# schematic.net
KiCad netlist of a schematic drawn in Altium Designer
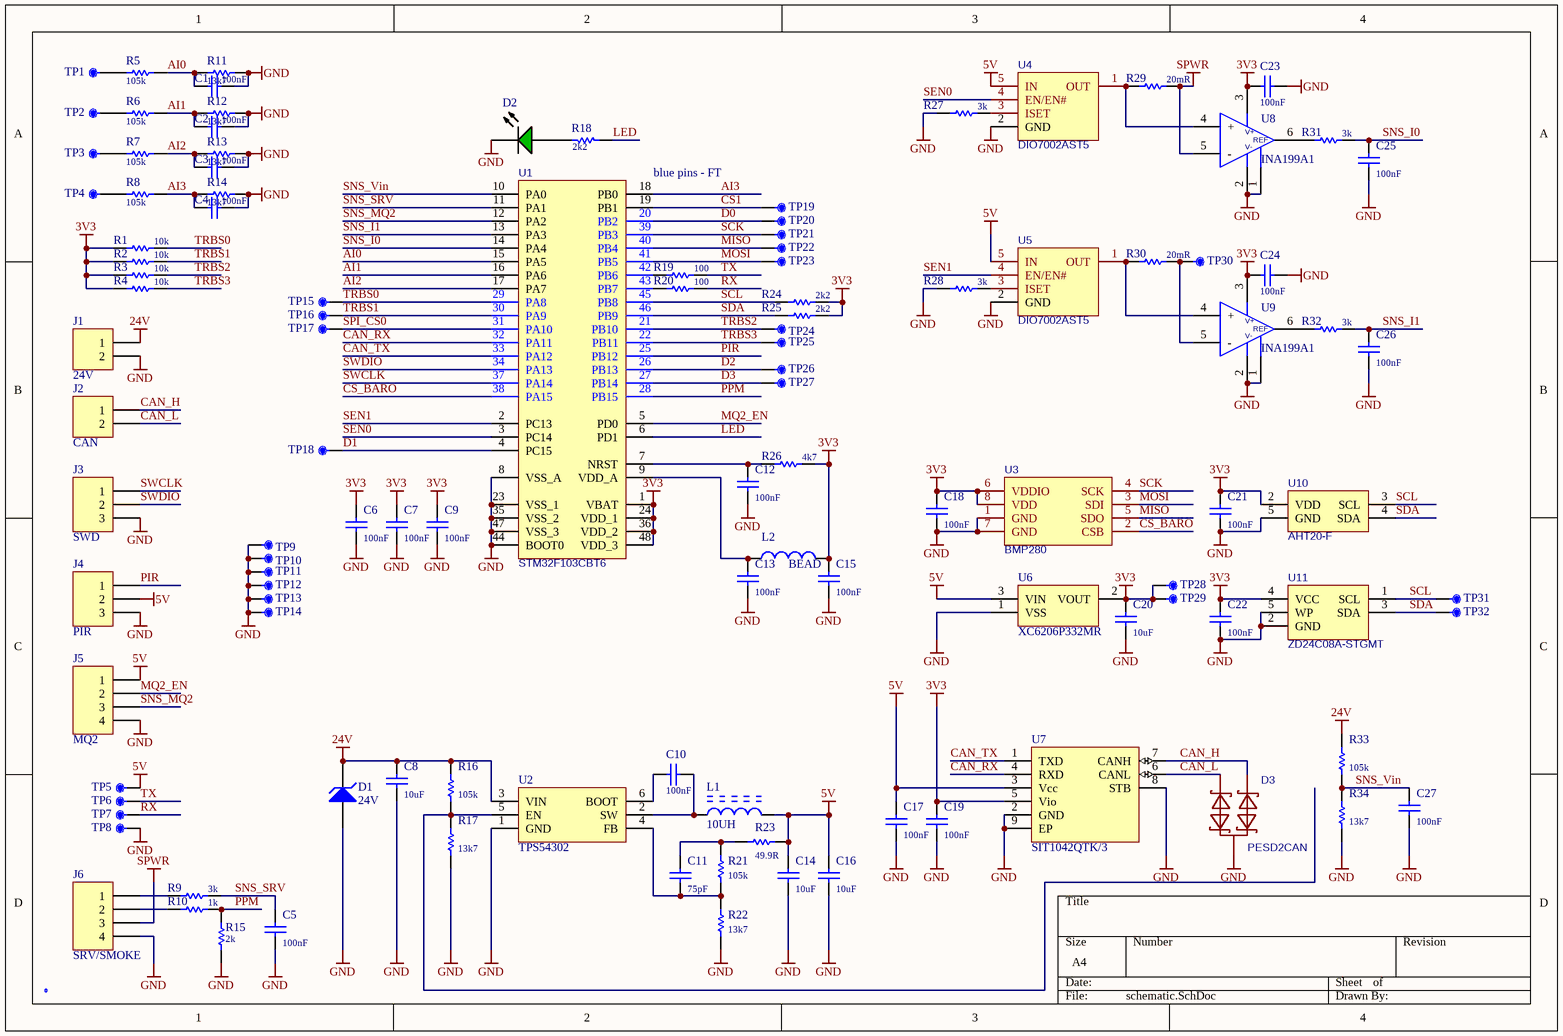
[diagram p0: schematic.SchDoc]

(export (version "E")
  (design (tool "Eeschema 10.0.6"))
  (components
    (comp (ref "C1")
      (value "100nF")
      (footprint "C0402")
      (description "100nF 50V 0402")
      (fields (field (name "LCSC PART NUMBER") "C110251"))
      (libsource (lib "Miscellaneous Devices") (part "CAP"))
    )
    (comp (ref "C2")
      (value "100nF")
      (footprint "C0402")
      (description "100nF 50V 0402")
      (fields (field (name "LCSC PART NUMBER") "C110251"))
      (libsource (lib "Miscellaneous Devices") (part "CAP"))
    )
    (comp (ref "C3")
      (value "100nF")
      (footprint "C0402")
      (description "100nF 50V 0402")
      (fields (field (name "LCSC PART NUMBER") "C110251"))
      (libsource (lib "Miscellaneous Devices") (part "CAP"))
    )
    (comp (ref "C4")
      (value "100nF")
      (footprint "C0402")
      (description "100nF 50V 0402")
      (fields (field (name "LCSC PART NUMBER") "C110251"))
      (libsource (lib "Miscellaneous Devices") (part "CAP"))
    )
    (comp (ref "C5")
      (value "100nF")
      (footprint "C0402")
      (description "100nF 50V 0402")
      (fields (field (name "LCSC PART NUMBER") "C110251"))
      (libsource (lib "Miscellaneous Devices") (part "CAP"))
    )
    (comp (ref "C6")
      (value "100nF")
      (footprint "C0402")
      (description "100nF 50V 0402")
      (fields (field (name "LCSC PART NUMBER") "C110251"))
      (libsource (lib "Miscellaneous Devices") (part "CAP"))
    )
    (comp (ref "C7")
      (value "100nF")
      (footprint "C0402")
      (description "100nF 50V 0402")
      (fields (field (name "LCSC PART NUMBER") "C110251"))
      (libsource (lib "Miscellaneous Devices") (part "CAP"))
    )
    (comp (ref "C8")
      (value "10uF")
      (footprint "C1206")
      (description "10uf 50V 1206")
      (fields (field (name "LCSC PART NUMBER") "C89632"))
      (libsource (lib "Miscellaneous Devices") (part "CAP"))
    )
    (comp (ref "C9")
      (value "100nF")
      (footprint "C0402")
      (description "100nF 50V 0402")
      (fields (field (name "LCSC PART NUMBER") "C110251"))
      (libsource (lib "Miscellaneous Devices") (part "CAP"))
    )
    (comp (ref "C10")
      (value "100nF")
      (footprint "C0402")
      (description "100nF 50V 0402")
      (fields (field (name "LCSC PART NUMBER") "C110251"))
      (libsource (lib "Miscellaneous Devices") (part "CAP"))
    )
    (comp (ref "C11")
      (value "75pF")
      (footprint "C0402")
      (description "75pF 50V 0402")
      (fields (field (name "LCSC PART NUMBER") "C107010"))
      (libsource (lib "Miscellaneous Devices") (part "CAP"))
    )
    (comp (ref "C12")
      (value "100nF")
      (footprint "C0402")
      (description "100nF 50V 0402")
      (fields (field (name "LCSC PART NUMBER") "C110251"))
      (libsource (lib "Miscellaneous Devices") (part "CAP"))
    )
    (comp (ref "C13")
      (value "100nF")
      (footprint "C0402")
      (description "100nF 50V 0402")
      (fields (field (name "LCSC PART NUMBER") "C110251"))
      (libsource (lib "Miscellaneous Devices") (part "CAP"))
    )
    (comp (ref "C14")
      (value "10uF")
      (footprint "C1206")
      (description "10uf 50V 1206")
      (fields (field (name "LCSC PART NUMBER") "C89632"))
      (libsource (lib "Miscellaneous Devices") (part "CAP"))
    )
    (comp (ref "C15")
      (value "100nF")
      (footprint "C0402")
      (description "100nF 50V 0402")
      (fields (field (name "LCSC PART NUMBER") "C110251"))
      (libsource (lib "Miscellaneous Devices") (part "CAP"))
    )
    (comp (ref "C16")
      (value "10uF")
      (footprint "C1206")
      (description "10uf 50V 1206")
      (fields (field (name "LCSC PART NUMBER") "C89632"))
      (libsource (lib "Miscellaneous Devices") (part "CAP"))
    )
    (comp (ref "C17")
      (value "100nF")
      (footprint "C0402")
      (description "100nF 50V 0402")
      (fields (field (name "LCSC PART NUMBER") "C110251"))
      (libsource (lib "Miscellaneous Devices") (part "CAP"))
    )
    (comp (ref "C18")
      (value "100nF")
      (footprint "C0402")
      (description "100nF 50V 0402")
      (fields (field (name "LCSC PART NUMBER") "C110251"))
      (libsource (lib "Miscellaneous Devices") (part "CAP"))
    )
    (comp (ref "C19")
      (value "100nF")
      (footprint "C0402")
      (description "100nF 50V 0402")
      (fields (field (name "LCSC PART NUMBER") "C110251"))
      (libsource (lib "Miscellaneous Devices") (part "CAP"))
    )
    (comp (ref "C20")
      (value "10uF")
      (footprint "C1206")
      (description "10uf 50V 1206")
      (fields (field (name "LCSC PART NUMBER") "C89632"))
      (libsource (lib "Miscellaneous Devices") (part "CAP"))
    )
    (comp (ref "C21")
      (value "100nF")
      (footprint "C0402")
      (description "100nF 50V 0402")
      (fields (field (name "LCSC PART NUMBER") "C110251"))
      (libsource (lib "Miscellaneous Devices") (part "CAP"))
    )
    (comp (ref "C22")
      (value "100nF")
      (footprint "C0402")
      (description "100nF 50V 0402")
      (fields (field (name "LCSC PART NUMBER") "C110251"))
      (libsource (lib "Miscellaneous Devices") (part "CAP"))
    )
    (comp (ref "C23")
      (value "100nF")
      (footprint "C0402")
      (description "100nF 50V 0402")
      (fields (field (name "LCSC PART NUMBER") "C110251"))
      (libsource (lib "Miscellaneous Devices") (part "CAP"))
    )
    (comp (ref "C24")
      (value "100nF")
      (footprint "C0402")
      (description "100nF 50V 0402")
      (fields (field (name "LCSC PART NUMBER") "C110251"))
      (libsource (lib "Miscellaneous Devices") (part "CAP"))
    )
    (comp (ref "C25")
      (value "100nF")
      (footprint "C0402")
      (description "100nF 50V 0402")
      (fields (field (name "LCSC PART NUMBER") "C110251"))
      (libsource (lib "Miscellaneous Devices") (part "CAP"))
    )
    (comp (ref "C26")
      (value "100nF")
      (footprint "C0402")
      (description "100nF 50V 0402")
      (fields (field (name "LCSC PART NUMBER") "C110251"))
      (libsource (lib "Miscellaneous Devices") (part "CAP"))
    )
    (comp (ref "C27")
      (value "100nF")
      (footprint "C0402")
      (description "100nF 50V 0402")
      (fields (field (name "LCSC PART NUMBER") "C110251"))
      (libsource (lib "Miscellaneous Devices") (part "CAP"))
    )
    (comp (ref "D1")
      (value "24V")
      (footprint "SMB")
      (description "P6SMB24A")
      (fields (field (name "LCSC PART NUMBER") "C5155417"))
      (libsource (lib "Miscellaneous Devices") (part "SMCJ54A"))
    )
    (comp (ref "D2")
      (value "GRN")
      (footprint "LED-0603-GRN")
      (description "LED 0603 GRN")
      (fields (field (name "LCSC PART NUMBER") "C434423"))
      (libsource (lib "Miscellaneous Devices") (part "LED-0603-GREEN"))
    )
    (comp (ref "D3")
      (value "PESD2CAN")
      (footprint "SOT-23")
      (fields (field (name "LCSC PART NUMBER") "C5261081"))
      (libsource (lib "Miscellaneous Devices") (part "CDSOT23-SM712"))
    )
    (comp (ref "J1")
      (value "24V")
      (footprint "CONN_DG308-2.54-2P")
      (description "DG308-2.54-02P-14-00A(H)")
      (fields (field (name "LCSC PART NUMBER") "C699496"))
      (libsource (lib "Miscellaneous Devices") (part "CONN MOLEX HDR-M 1x4"))
    )
    (comp (ref "J2")
      (value "CAN")
      (footprint "CONN_DG308-2.54-2P")
      (description "DG308-2.54-02P-14-00A(H)")
      (fields (field (name "LCSC PART NUMBER") "C699496"))
      (libsource (lib "Miscellaneous Devices") (part "CONN MOLEX HDR-M 1x4"))
    )
    (comp (ref "J3")
      (value "SWD")
      (footprint "SWD")
      (libsource (lib "Miscellaneous Devices") (part "Header 3"))
    )
    (comp (ref "J4")
      (value "PIR")
      (footprint "CONN_MOLEX_532610371")
      (libsource (lib "Miscellaneous Devices") (part "Header 3"))
    )
    (comp (ref "J5")
      (value "MQ2")
      (footprint "CONN_MOLEX_532610471")
      (libsource (lib "Schlib1") (part "Header 3"))
    )
    (comp (ref "J6") (value "SRV/SMOKE") (footprint "HDR-1X4") (libsource (lib "Schlib1") (part "Header 3")))
    (comp (ref "L1")
      (value "10UH")
      (footprint "IND-SMD_L7.2-W6.6_GPSR07X0")
      (description "CYA0630-10UH")
      (fields (field (name "LCSC PART NUMBER") "C5189958"))
      (libsource (lib "Miscellaneous Devices") (part "SRN3015-100M"))
    )
    (comp (ref "L2")
      (value "BEAD")
      (footprint "L0402")
      (description "BEAD 0402")
      (fields (field (name "LCSC PART NUMBER") "C76883"))
      (libsource (lib "Miscellaneous Devices") (part "BLM18AG601SN1D"))
    )
    (comp (ref "LOGO1") (value "LOGO") (footprint "LOGO") (libsource (lib "Schlib1") (part "LOGO")))
    (comp (ref "R1")
      (value "10k")
      (footprint "R0402")
      (description "10k 0402")
      (fields (field (name "LCSC PART NUMBER") "C25744"))
      (libsource (lib "Miscellaneous Devices") (part "RES"))
    )
    (comp (ref "R2")
      (value "10k")
      (footprint "R0402")
      (description "10k 0402")
      (fields (field (name "LCSC PART NUMBER") "C25744"))
      (libsource (lib "Miscellaneous Devices") (part "RES"))
    )
    (comp (ref "R3")
      (value "10k")
      (footprint "R0402")
      (description "10k 0402")
      (fields (field (name "LCSC PART NUMBER") "C25744"))
      (libsource (lib "Miscellaneous Devices") (part "RES"))
    )
    (comp (ref "R4")
      (value "10k")
      (footprint "R0402")
      (description "10k 0402")
      (fields (field (name "LCSC PART NUMBER") "C25744"))
      (libsource (lib "Miscellaneous Devices") (part "RES"))
    )
    (comp (ref "R5")
      (value "105k")
      (footprint "R0402")
      (description "105k 0402")
      (fields (field (name "LCSC PART NUMBER") "C170210"))
      (libsource (lib "Miscellaneous Devices") (part "RES"))
    )
    (comp (ref "R6")
      (value "105k")
      (footprint "R0402")
      (description "105k 0402")
      (fields (field (name "LCSC PART NUMBER") "C170210"))
      (libsource (lib "Miscellaneous Devices") (part "RES"))
    )
    (comp (ref "R7")
      (value "105k")
      (footprint "R0402")
      (description "105k 0402")
      (fields (field (name "LCSC PART NUMBER") "C170210"))
      (libsource (lib "Miscellaneous Devices") (part "RES"))
    )
    (comp (ref "R8")
      (value "105k")
      (footprint "R0402")
      (description "105k 0402")
      (fields (field (name "LCSC PART NUMBER") "C170210"))
      (libsource (lib "Miscellaneous Devices") (part "RES"))
    )
    (comp (ref "R9")
      (value "3k")
      (footprint "R0402")
      (description "3k 0402")
      (fields (field (name "LCSC PART NUMBER") "C25784"))
      (libsource (lib "") (part "RES_1"))
    )
    (comp (ref "R10")
      (value "1k")
      (footprint "R0402")
      (description "1k 0402")
      (fields (field (name "LCSC PART NUMBER") "C11702"))
      (libsource (lib "Miscellaneous Devices") (part "RES"))
    )
    (comp (ref "R11")
      (value "13k7")
      (footprint "R0402")
      (description "13k7 0402")
      (fields (field (name "LCSC PART NUMBER") "C2933072"))
      (libsource (lib "Miscellaneous Devices") (part "RES"))
    )
    (comp (ref "R12")
      (value "13k7")
      (footprint "R0402")
      (description "13k7 0402")
      (fields (field (name "LCSC PART NUMBER") "C2933072"))
      (libsource (lib "Miscellaneous Devices") (part "RES"))
    )
    (comp (ref "R13")
      (value "13k7")
      (footprint "R0402")
      (description "13k7 0402")
      (fields (field (name "LCSC PART NUMBER") "C2933072"))
      (libsource (lib "Miscellaneous Devices") (part "RES"))
    )
    (comp (ref "R14")
      (value "13k7")
      (footprint "R0402")
      (description "13k7 0402")
      (fields (field (name "LCSC PART NUMBER") "C2933072"))
      (libsource (lib "Miscellaneous Devices") (part "RES"))
    )
    (comp (ref "R15")
      (value "2k")
      (footprint "R0402")
      (description "2k 0402")
      (fields (field (name "LCSC PART NUMBER") "C4109"))
      (libsource (lib "Miscellaneous Devices") (part "RES"))
    )
    (comp (ref "R16")
      (value "105k")
      (footprint "R0402")
      (description "105k 0402")
      (fields (field (name "LCSC PART NUMBER") "C170210"))
      (libsource (lib "Miscellaneous Devices") (part "RES"))
    )
    (comp (ref "R17")
      (value "13k7")
      (footprint "R0402")
      (description "13k7 0402")
      (fields (field (name "LCSC PART NUMBER") "C2933072"))
      (libsource (lib "Miscellaneous Devices") (part "RES"))
    )
    (comp (ref "R18")
      (value "2k2")
      (footprint "R0402")
      (description "2k 0402")
      (fields (field (name "LCSC PART NUMBER") "C4109"))
      (libsource (lib "Miscellaneous Devices") (part "RES"))
    )
    (comp (ref "R19")
      (value "100")
      (footprint "R0402")
      (description "100 0402")
      (fields (field (name "LCSC PART NUMBER") "C25076"))
      (libsource (lib "Miscellaneous Devices") (part "RES"))
    )
    (comp (ref "R20")
      (value "100")
      (footprint "R0402")
      (description "100 0402")
      (fields (field (name "LCSC PART NUMBER") "C25076"))
      (libsource (lib "Miscellaneous Devices") (part "RES"))
    )
    (comp (ref "R21")
      (value "105k")
      (footprint "R0402")
      (description "105k 0402")
      (fields (field (name "LCSC PART NUMBER") "C170210"))
      (libsource (lib "Miscellaneous Devices") (part "RES"))
    )
    (comp (ref "R22")
      (value "13k7")
      (footprint "R0402")
      (description "13k7 0402")
      (fields (field (name "LCSC PART NUMBER") "C2933072"))
      (libsource (lib "Miscellaneous Devices") (part "RES"))
    )
    (comp (ref "R23")
      (value "49.9R")
      (footprint "R0402")
      (description "49R9 0402")
      (fields (field (name "LCSC PART NUMBER") "C87044"))
      (libsource (lib "") (part "RES_2"))
    )
    (comp (ref "R24")
      (value "2k2")
      (footprint "R0402")
      (description "2k 0402")
      (fields (field (name "LCSC PART NUMBER") "C4109"))
      (libsource (lib "Miscellaneous Devices") (part "RES"))
    )
    (comp (ref "R25")
      (value "2k2")
      (footprint "R0402")
      (description "2k 0402")
      (fields (field (name "LCSC PART NUMBER") "C4109"))
      (libsource (lib "Miscellaneous Devices") (part "RES"))
    )
    (comp (ref "R26")
      (value "4k7")
      (footprint "R0402")
      (description "4k7 0402")
      (fields (field (name "LCSC PART NUMBER") "C25900"))
      (libsource (lib "Miscellaneous Devices") (part "RES"))
    )
    (comp (ref "R27")
      (value "3k")
      (footprint "R0402")
      (description "3k 0402")
      (fields (field (name "LCSC PART NUMBER") "C25784"))
      (libsource (lib "") (part "RES_1"))
    )
    (comp (ref "R28")
      (value "3k")
      (footprint "R0402")
      (description "3k 0402")
      (fields (field (name "LCSC PART NUMBER") "C25784"))
      (libsource (lib "") (part "RES_1"))
    )
    (comp (ref "R29")
      (value "20mR")
      (footprint "R0805")
      (description "0805W4F200MT5E")
      (fields (field (name "LCSC PART NUMBER") "C7467520"))
      (libsource (lib "") (part "RES_1"))
    )
    (comp (ref "R30")
      (value "20mR")
      (footprint "R0805")
      (description "0805W4F200MT5E")
      (fields (field (name "LCSC PART NUMBER") "C7467520"))
      (libsource (lib "") (part "RES_1"))
    )
    (comp (ref "R31")
      (value "3k")
      (footprint "R0402")
      (description "3k 0402")
      (fields (field (name "LCSC PART NUMBER") "C25784"))
      (libsource (lib "Miscellaneous Devices") (part "RES"))
    )
    (comp (ref "R32")
      (value "3k")
      (footprint "R0402")
      (description "3k 0402")
      (fields (field (name "LCSC PART NUMBER") "C25784"))
      (libsource (lib "Miscellaneous Devices") (part "RES"))
    )
    (comp (ref "R33")
      (value "105k")
      (footprint "R0402")
      (description "105k 0402")
      (fields (field (name "LCSC PART NUMBER") "C170210"))
      (libsource (lib "Miscellaneous Devices") (part "RES"))
    )
    (comp (ref "R34")
      (value "13k7")
      (footprint "R0402")
      (description "13k7 0402")
      (fields (field (name "LCSC PART NUMBER") "C2933072"))
      (libsource (lib "Miscellaneous Devices") (part "RES"))
    )
    (comp (ref "TP1")
      (value "~")
      (footprint "TP_TH_S0")
      (libsource (lib "Miscellaneous Devices") (part "TP_Dup1"))
    )
    (comp (ref "TP2")
      (value "~")
      (footprint "TP_TH_S0")
      (libsource (lib "Miscellaneous Devices") (part "TP_Dup1"))
    )
    (comp (ref "TP3")
      (value "~")
      (footprint "TP_TH_S0")
      (libsource (lib "Miscellaneous Devices") (part "TP_Dup1"))
    )
    (comp (ref "TP4")
      (value "~")
      (footprint "TP_TH_S0")
      (libsource (lib "Miscellaneous Devices") (part "TP_Dup1"))
    )
    (comp (ref "TP5")
      (value "~")
      (footprint "TP_TH_S0")
      (libsource (lib "Miscellaneous Devices") (part "TP_Dup1"))
    )
    (comp (ref "TP6")
      (value "~")
      (footprint "TP_TH_S0")
      (libsource (lib "Miscellaneous Devices") (part "TP_Dup1"))
    )
    (comp (ref "TP7")
      (value "~")
      (footprint "TP_TH_S0")
      (libsource (lib "Miscellaneous Devices") (part "TP_Dup1"))
    )
    (comp (ref "TP8")
      (value "~")
      (footprint "TP_TH_S0")
      (libsource (lib "Miscellaneous Devices") (part "TP_Dup1"))
    )
    (comp (ref "TP9")
      (value "~")
      (footprint "TP_TH_S0")
      (libsource (lib "Miscellaneous Devices") (part "TP_Dup1"))
    )
    (comp (ref "TP10")
      (value "~")
      (footprint "TP_TH_S0")
      (libsource (lib "Miscellaneous Devices") (part "TP_Dup1"))
    )
    (comp (ref "TP11")
      (value "~")
      (footprint "TP_TH_S0")
      (libsource (lib "Miscellaneous Devices") (part "TP_Dup1"))
    )
    (comp (ref "TP12")
      (value "~")
      (footprint "TP_TH_S0")
      (libsource (lib "Miscellaneous Devices") (part "TP_Dup1"))
    )
    (comp (ref "TP13")
      (value "~")
      (footprint "TP_TH_S0")
      (libsource (lib "Miscellaneous Devices") (part "TP_Dup1"))
    )
    (comp (ref "TP14")
      (value "~")
      (footprint "TP_TH_S0")
      (libsource (lib "Miscellaneous Devices") (part "TP_Dup1"))
    )
    (comp (ref "TP15")
      (value "~")
      (footprint "TP_TH_S0")
      (libsource (lib "Miscellaneous Devices") (part "TP_Dup1"))
    )
    (comp (ref "TP16")
      (value "~")
      (footprint "TP_TH_S0")
      (libsource (lib "Miscellaneous Devices") (part "TP_Dup1"))
    )
    (comp (ref "TP17")
      (value "~")
      (footprint "TP_TH_S0")
      (libsource (lib "Miscellaneous Devices") (part "TP_Dup1"))
    )
    (comp (ref "TP18")
      (value "~")
      (footprint "TP_TH_S0")
      (libsource (lib "Miscellaneous Devices") (part "TP_Dup1"))
    )
    (comp (ref "TP19")
      (value "~")
      (footprint "TP_TH_S0")
      (libsource (lib "Miscellaneous Devices") (part "TP_Dup1"))
    )
    (comp (ref "TP20")
      (value "~")
      (footprint "TP_TH_S0")
      (libsource (lib "Miscellaneous Devices") (part "TP_Dup1"))
    )
    (comp (ref "TP21")
      (value "~")
      (footprint "TP_TH_S0")
      (libsource (lib "Miscellaneous Devices") (part "TP_Dup1"))
    )
    (comp (ref "TP22")
      (value "~")
      (footprint "TP_TH_S0")
      (libsource (lib "Miscellaneous Devices") (part "TP_Dup1"))
    )
    (comp (ref "TP23")
      (value "~")
      (footprint "TP_TH_S0")
      (libsource (lib "Miscellaneous Devices") (part "TP_Dup1"))
    )
    (comp (ref "TP24")
      (value "~")
      (footprint "TP_TH_S0")
      (libsource (lib "Miscellaneous Devices") (part "TP_Dup1"))
    )
    (comp (ref "TP25")
      (value "~")
      (footprint "TP_TH_S0")
      (libsource (lib "Miscellaneous Devices") (part "TP_Dup1"))
    )
    (comp (ref "TP26")
      (value "~")
      (footprint "TP_TH_S0")
      (libsource (lib "Miscellaneous Devices") (part "TP_Dup1"))
    )
    (comp (ref "TP27")
      (value "~")
      (footprint "TP_TH_S0")
      (libsource (lib "Miscellaneous Devices") (part "TP_Dup1"))
    )
    (comp (ref "TP28")
      (value "~")
      (footprint "TP_TH_S0")
      (libsource (lib "Miscellaneous Devices") (part "TP_Dup1"))
    )
    (comp (ref "TP29")
      (value "~")
      (footprint "TP_TH_S0")
      (libsource (lib "Miscellaneous Devices") (part "TP_Dup1"))
    )
    (comp (ref "TP30")
      (value "~")
      (footprint "TP_TH_S0")
      (libsource (lib "Miscellaneous Devices") (part "TP_Dup1"))
    )
    (comp (ref "TP31")
      (value "~")
      (footprint "TP_TH_S0")
      (libsource (lib "Miscellaneous Devices") (part "TP_Dup1"))
    )
    (comp (ref "TP32")
      (value "~")
      (footprint "TP_TH_S0")
      (libsource (lib "Miscellaneous Devices") (part "TP_Dup1"))
    )
    (comp (ref "U1")
      (value "STM32F103CBT6")
      (footprint "LQFP-48")
      (fields (field (name "LCSC PART NUMBER") "C8304"))
      (libsource (lib "Schlib1") (part "STM32F103CBT6"))
    )
    (comp (ref "U2")
      (value "TPS54302")
      (footprint "SOT-23-6")
      (description "TPS54302DDCR")
      (fields (field (name "LCSC PART NUMBER") "C311983"))
      (libsource (lib "Miscellaneous Devices") (part "LM27313XMFX"))
    )
    (comp (ref "U3")
      (value "BMP280")
      (footprint "WLGA-8_L2.5-W2.0-P0.65-TR_DPS422")
      (fields (field (name "LCSC PART NUMBER") "C83291"))
      (libsource (lib "Schlib1") (part "BMP280"))
    )
    (comp (ref "U4")
      (value "DIO7002AST5")
      (footprint "SOT-23-5")
      (fields (field (name "LCSC PART NUMBER") "C403840"))
      (libsource (lib "Schlib1") (part "DIO7002AST5"))
    )
    (comp (ref "U5")
      (value "DIO7002AST5")
      (footprint "SOT-23-5")
      (fields (field (name "LCSC PART NUMBER") "C403840"))
      (libsource (lib "Schlib1") (part "DIO7002AST5"))
    )
    (comp (ref "U6")
      (value "XC6206P332MR")
      (footprint "SOT-23")
      (fields (field (name "LCSC PART NUMBER") "C5148692"))
      (libsource (lib "Schlib1") (part "Component_4_1"))
    )
    (comp (ref "U7")
      (value "SIT1042QTK/3")
      (footprint "DFN8_3X3_P065")
      (description "IC INTERFACE CAN")
      (fields (field (name "LCSC PART NUMBER") "C5308062"))
      (libsource (lib "Miscellaneous Devices") (part "LTC2875"))
    )
    (comp (ref "U8")
      (value "INA199A1")
      (footprint "SOT-363")
      (fields (field (name "LCSC PART NUMBER") "C59135"))
      (libsource (lib "Miscellaneous Devices") (part "MCP65R41T-2402"))
    )
    (comp (ref "U9")
      (value "INA199A1")
      (footprint "SOT-363")
      (fields (field (name "LCSC PART NUMBER") "C59135"))
      (libsource (lib "Miscellaneous Devices") (part "MCP65R41T-2402"))
    )
    (comp (ref "U10")
      (value "AHT20-F")
      (footprint "SENSOR-SMD_L3.0-W3.0-P1.00-BR")
      (description "AHT20-F ¦ HDC1080DMBR ¦ AHT21")
      (fields (field (name "LCSC PART NUMBER") "C3012622"))
      (libsource (lib "Schlib1") (part "AHT21"))
    )
    (comp (ref "U11")
      (value "ZD24C08A-STGMT")
      (footprint "SOT-23-5")
      (fields (field (name "LCSC PART NUMBER") "C2896640"))
      (libsource (lib "Schlib1") (part "ZD24C08A-STGMT"))
    )
  )
  (nets
    (net (code "1") (name "/AI0") (class "Default")
      (node (ref "C1") (pin "2") (pinfunction "2_2") (pintype "passive"))
      (node (ref "R11") (pin "1") (pinfunction "1_1") (pintype "passive"))
      (node (ref "R5") (pin "2") (pinfunction "2_2") (pintype "passive"))
      (node (ref "U1") (pin "15") (pinfunction "PA5_15") (pintype "passive"))
    )
    (net (code "2") (name "/AI1") (class "Default")
      (node (ref "C2") (pin "2") (pinfunction "2_2") (pintype "passive"))
      (node (ref "R12") (pin "1") (pinfunction "1_1") (pintype "passive"))
      (node (ref "R6") (pin "2") (pinfunction "2_2") (pintype "passive"))
      (node (ref "U1") (pin "16") (pinfunction "PA6_16") (pintype "passive"))
    )
    (net (code "3") (name "/AI2") (class "Default")
      (node (ref "C3") (pin "2") (pinfunction "2_2") (pintype "passive"))
      (node (ref "R13") (pin "1") (pinfunction "1_1") (pintype "passive"))
      (node (ref "R7") (pin "2") (pinfunction "2_2") (pintype "passive"))
      (node (ref "U1") (pin "17") (pinfunction "PA7_17") (pintype "passive"))
    )
    (net (code "4") (name "/AI3") (class "Default")
      (node (ref "C4") (pin "2") (pinfunction "2_2") (pintype "passive"))
      (node (ref "R14") (pin "1") (pinfunction "1_1") (pintype "passive"))
      (node (ref "R8") (pin "2") (pinfunction "2_2") (pintype "passive"))
      (node (ref "U1") (pin "18") (pinfunction "PB0_18") (pintype "passive"))
    )
    (net (code "5") (name "/CAN_H") (class "Default")
      (node (ref "D3") (pin "2") (pinfunction "2_2") (pintype "passive"))
      (node (ref "J2") (pin "1") (pinfunction "1_1") (pintype "passive"))
      (node (ref "U7") (pin "7") (pinfunction "CANH_7") (pintype "bidirectional"))
    )
    (net (code "6") (name "/CAN_L") (class "Default")
      (node (ref "D3") (pin "1") (pinfunction "1_1") (pintype "passive"))
      (node (ref "J2") (pin "2") (pinfunction "2_2") (pintype "passive"))
      (node (ref "U7") (pin "6") (pinfunction "CANL_6") (pintype "bidirectional"))
    )
    (net (code "7") (name "/CAN_RX") (class "Default")
      (node (ref "U1") (pin "32") (pinfunction "PA11_32") (pintype "passive"))
      (node (ref "U7") (pin "4") (pinfunction "RXD_4") (pintype "passive"))
    )
    (net (code "8") (name "/CAN_TX") (class "Default")
      (node (ref "U1") (pin "33") (pinfunction "PA12_33") (pintype "passive"))
      (node (ref "U7") (pin "1") (pinfunction "TXD_1") (pintype "passive"))
    )
    (net (code "9") (name "/CS1") (class "Default")
      (node (ref "TP19") (pin "1") (pinfunction "1_1") (pintype "passive"))
      (node (ref "U1") (pin "19") (pinfunction "PB1_19") (pintype "passive"))
    )
    (net (code "10") (name "/CS_BARO") (class "Default")
      (node (ref "U1") (pin "38") (pinfunction "PA15_38") (pintype "passive"))
      (node (ref "U3") (pin "2") (pinfunction "CSB_2") (pintype "passive"))
    )
    (net (code "11") (name "/D0") (class "Default")
      (node (ref "TP20") (pin "1") (pinfunction "1_1") (pintype "passive"))
      (node (ref "U1") (pin "20") (pinfunction "PB2_20") (pintype "passive"))
    )
    (net (code "12") (name "/D1") (class "Default")
      (node (ref "TP18") (pin "1") (pinfunction "1_1") (pintype "passive"))
      (node (ref "U1") (pin "4") (pinfunction "PC15_4") (pintype "passive"))
    )
    (net (code "13") (name "/D2") (class "Default")
      (node (ref "TP26") (pin "1") (pinfunction "1_1") (pintype "passive"))
      (node (ref "U1") (pin "26") (pinfunction "PB13_26") (pintype "passive"))
    )
    (net (code "14") (name "/D3") (class "Default")
      (node (ref "TP27") (pin "1") (pinfunction "1_1") (pintype "passive"))
      (node (ref "U1") (pin "27") (pinfunction "PB14_27") (pintype "passive"))
    )
    (net (code "15") (name "/LED") (class "Default")
      (node (ref "R18") (pin "2") (pinfunction "2_2") (pintype "passive"))
      (node (ref "U1") (pin "6") (pinfunction "PD1_6") (pintype "passive"))
    )
    (net (code "16") (name "/MISO") (class "Default")
      (node (ref "TP22") (pin "1") (pinfunction "1_1") (pintype "passive"))
      (node (ref "U1") (pin "40") (pinfunction "PB4_40") (pintype "passive"))
      (node (ref "U3") (pin "5") (pinfunction "SDO_5") (pintype "passive"))
    )
    (net (code "17") (name "/MOSI") (class "Default")
      (node (ref "TP23") (pin "1") (pinfunction "1_1") (pintype "passive"))
      (node (ref "U1") (pin "41") (pinfunction "PB5_41") (pintype "passive"))
      (node (ref "U3") (pin "3") (pinfunction "SDI_3") (pintype "passive"))
    )
    (net (code "18") (name "/MQ2_EN") (class "Default")
      (node (ref "J5") (pin "2") (pinfunction "2_2") (pintype "passive"))
      (node (ref "U1") (pin "5") (pinfunction "PD0_5") (pintype "passive"))
    )
    (net (code "19") (name "/PIR") (class "Default")
      (node (ref "J4") (pin "1") (pinfunction "1_1") (pintype "passive"))
      (node (ref "U1") (pin "25") (pinfunction "PB12_25") (pintype "passive"))
    )
    (net (code "20") (name "/PPM") (class "Default")
      (node (ref "R10") (pin "1") (pinfunction "1_1") (pintype "passive"))
      (node (ref "R15") (pin "1") (pinfunction "1_1") (pintype "passive"))
      (node (ref "U1") (pin "28") (pinfunction "PB15_28") (pintype "passive"))
    )
    (net (code "21") (name "/RX") (class "Default")
      (node (ref "R20") (pin "1") (pinfunction "1_1") (pintype "passive"))
      (node (ref "TP7") (pin "1") (pinfunction "1_1") (pintype "passive"))
    )
    (net (code "22") (name "/SCK") (class "Default")
      (node (ref "TP21") (pin "1") (pinfunction "1_1") (pintype "passive"))
      (node (ref "U1") (pin "39") (pinfunction "PB3_39") (pintype "passive"))
      (node (ref "U3") (pin "4") (pinfunction "SCK_4") (pintype "passive"))
    )
    (net (code "23") (name "/SCL") (class "Default")
      (node (ref "R24") (pin "1") (pinfunction "1_1") (pintype "passive"))
      (node (ref "TP31") (pin "1") (pinfunction "1_1") (pintype "passive"))
      (node (ref "U1") (pin "45") (pinfunction "PB8_45") (pintype "passive"))
      (node (ref "U10") (pin "3") (pinfunction "SCL_3") (pintype "passive"))
      (node (ref "U11") (pin "1") (pinfunction "SCL_1") (pintype "passive"))
    )
    (net (code "24") (name "/SDA") (class "Default")
      (node (ref "R25") (pin "1") (pinfunction "1_1") (pintype "passive"))
      (node (ref "TP32") (pin "1") (pinfunction "1_1") (pintype "passive"))
      (node (ref "U1") (pin "46") (pinfunction "PB9_46") (pintype "passive"))
      (node (ref "U10") (pin "4") (pinfunction "SDA_4") (pintype "passive"))
      (node (ref "U11") (pin "3") (pinfunction "SDA_3") (pintype "passive"))
    )
    (net (code "25") (name "/SEN0") (class "Default")
      (node (ref "U1") (pin "3") (pinfunction "PC14_3") (pintype "passive"))
      (node (ref "U4") (pin "4") (pinfunction "EN/EN#_4") (pintype "passive"))
    )
    (net (code "26") (name "/SEN1") (class "Default")
      (node (ref "U1") (pin "2") (pinfunction "PC13_2") (pintype "passive"))
      (node (ref "U5") (pin "4") (pinfunction "EN/EN#_4") (pintype "passive"))
    )
    (net (code "27") (name "/SNS_I0") (class "Default")
      (node (ref "C25") (pin "2") (pinfunction "2_2") (pintype "passive"))
      (node (ref "R31") (pin "1") (pinfunction "1_1") (pintype "passive"))
      (node (ref "U1") (pin "14") (pinfunction "PA4_14") (pintype "passive"))
    )
    (net (code "28") (name "/SNS_I1") (class "Default")
      (node (ref "C26") (pin "2") (pinfunction "2_2") (pintype "passive"))
      (node (ref "R32") (pin "1") (pinfunction "1_1") (pintype "passive"))
      (node (ref "U1") (pin "13") (pinfunction "PA3_13") (pintype "passive"))
    )
    (net (code "29") (name "/SNS_MQ2") (class "Default")
      (node (ref "J5") (pin "3") (pinfunction "3_3") (pintype "passive"))
      (node (ref "U1") (pin "12") (pinfunction "PA2_12") (pintype "passive"))
    )
    (net (code "30") (name "/SNS_SRV") (class "Default")
      (node (ref "C5") (pin "2") (pinfunction "2_2") (pintype "passive"))
      (node (ref "R9") (pin "1") (pinfunction "1_1") (pintype "passive"))
      (node (ref "U1") (pin "11") (pinfunction "PA1_11") (pintype "passive"))
    )
    (net (code "31") (name "/SNS_Vin") (class "Default")
      (node (ref "C27") (pin "2") (pinfunction "2_2") (pintype "passive"))
      (node (ref "R33") (pin "2") (pinfunction "2_2") (pintype "passive"))
      (node (ref "R34") (pin "1") (pinfunction "1_1") (pintype "passive"))
      (node (ref "U1") (pin "10") (pinfunction "PA0_10") (pintype "passive"))
    )
    (net (code "32") (name "/SPI_CS0") (class "Default")
      (node (ref "TP17") (pin "1") (pinfunction "1_1") (pintype "passive"))
      (node (ref "U1") (pin "31") (pinfunction "PA10_31") (pintype "passive"))
    )
    (net (code "33") (name "/SWCLK") (class "Default")
      (node (ref "J3") (pin "1") (pinfunction "1_1") (pintype "passive"))
      (node (ref "U1") (pin "37") (pinfunction "PA14_37") (pintype "passive"))
    )
    (net (code "34") (name "/SWDIO") (class "Default")
      (node (ref "J3") (pin "2") (pinfunction "2_2") (pintype "passive"))
      (node (ref "U1") (pin "34") (pinfunction "PA13_34") (pintype "passive"))
    )
    (net (code "35") (name "/TRBS0") (class "Default")
      (node (ref "R1") (pin "1") (pinfunction "1_1") (pintype "passive"))
      (node (ref "TP15") (pin "1") (pinfunction "1_1") (pintype "passive"))
      (node (ref "U1") (pin "29") (pinfunction "PA8_29") (pintype "passive"))
    )
    (net (code "36") (name "/TRBS1") (class "Default")
      (node (ref "R2") (pin "1") (pinfunction "1_1") (pintype "passive"))
      (node (ref "TP16") (pin "1") (pinfunction "1_1") (pintype "passive"))
      (node (ref "U1") (pin "30") (pinfunction "PA9_30") (pintype "passive"))
    )
    (net (code "37") (name "/TRBS2") (class "Default")
      (node (ref "R3") (pin "1") (pinfunction "1_1") (pintype "passive"))
      (node (ref "TP24") (pin "1") (pinfunction "1_1") (pintype "passive"))
      (node (ref "U1") (pin "21") (pinfunction "PB10_21") (pintype "passive"))
    )
    (net (code "38") (name "/TRBS3") (class "Default")
      (node (ref "R4") (pin "1") (pinfunction "1_1") (pintype "passive"))
      (node (ref "TP25") (pin "1") (pinfunction "1_1") (pintype "passive"))
      (node (ref "U1") (pin "22") (pinfunction "PB11_22") (pintype "passive"))
    )
    (net (code "39") (name "/TX") (class "Default")
      (node (ref "R19") (pin "1") (pinfunction "1_1") (pintype "passive"))
      (node (ref "TP6") (pin "1") (pinfunction "1_1") (pintype "passive"))
    )
    (net (code "40") (name "3V3") (class "Default")
      (node (ref "C15") (pin "2") (pinfunction "2_2") (pintype "passive"))
      (node (ref "C18") (pin "2") (pinfunction "2_2") (pintype "passive"))
      (node (ref "C19") (pin "2") (pinfunction "2_2") (pintype "passive"))
      (node (ref "C20") (pin "2") (pinfunction "2_2") (pintype "passive"))
      (node (ref "C21") (pin "2") (pinfunction "2_2") (pintype "passive"))
      (node (ref "C22") (pin "2") (pinfunction "2_2") (pintype "passive"))
      (node (ref "C23") (pin "2") (pinfunction "2_2") (pintype "passive"))
      (node (ref "C24") (pin "2") (pinfunction "2_2") (pintype "passive"))
      (node (ref "C6") (pin "2") (pinfunction "2_2") (pintype "passive"))
      (node (ref "C7") (pin "2") (pinfunction "2_2") (pintype "passive"))
      (node (ref "C9") (pin "2") (pinfunction "2_2") (pintype "passive"))
      (node (ref "L2") (pin "1") (pinfunction "1_1") (pintype "passive"))
      (node (ref "R1") (pin "2") (pinfunction "2_2") (pintype "passive"))
      (node (ref "R2") (pin "2") (pinfunction "2_2") (pintype "passive"))
      (node (ref "R24") (pin "2") (pinfunction "2_2") (pintype "passive"))
      (node (ref "R25") (pin "2") (pinfunction "2_2") (pintype "passive"))
      (node (ref "R26") (pin "1") (pinfunction "1_1") (pintype "passive"))
      (node (ref "R3") (pin "2") (pinfunction "2_2") (pintype "passive"))
      (node (ref "R4") (pin "2") (pinfunction "2_2") (pintype "passive"))
      (node (ref "TP28") (pin "1") (pinfunction "1_1") (pintype "passive"))
      (node (ref "TP29") (pin "1") (pinfunction "1_1") (pintype "passive"))
      (node (ref "U1") (pin "1") (pinfunction "VBAT_1") (pintype "passive"))
      (node (ref "U1") (pin "24") (pinfunction "VDD_1_24") (pintype "passive"))
      (node (ref "U1") (pin "36") (pinfunction "VDD_2_36") (pintype "passive"))
      (node (ref "U1") (pin "48") (pinfunction "VDD_3_48") (pintype "passive"))
      (node (ref "U10") (pin "2") (pinfunction "VDD_2") (pintype "passive"))
      (node (ref "U11") (pin "4") (pinfunction "VCC_4") (pintype "passive"))
      (node (ref "U3") (pin "6") (pinfunction "VDDIO_6") (pintype "passive"))
      (node (ref "U3") (pin "8") (pinfunction "VDD_8") (pintype "passive"))
      (node (ref "U6") (pin "2") (pinfunction "VOUT_2") (pintype "passive"))
      (node (ref "U7") (pin "5") (pinfunction "Vio_5") (pintype "passive"))
      (node (ref "U8") (pin "3") (pinfunction "V+_3") (pintype "passive"))
      (node (ref "U9") (pin "3") (pinfunction "V+_3") (pintype "passive"))
    )
    (net (code "41") (name "5V") (class "Default")
      (node (ref "C14") (pin "2") (pinfunction "2_2") (pintype "passive"))
      (node (ref "C16") (pin "2") (pinfunction "2_2") (pintype "passive"))
      (node (ref "C17") (pin "2") (pinfunction "2_2") (pintype "passive"))
      (node (ref "J4") (pin "2") (pinfunction "2_2") (pintype "passive"))
      (node (ref "J5") (pin "1") (pinfunction "1_1") (pintype "passive"))
      (node (ref "L1") (pin "2") (pinfunction "2_2") (pintype "passive"))
      (node (ref "R23") (pin "1") (pinfunction "1_1") (pintype "passive"))
      (node (ref "TP5") (pin "1") (pinfunction "1_1") (pintype "passive"))
      (node (ref "U4") (pin "5") (pinfunction "IN_5") (pintype "passive"))
      (node (ref "U5") (pin "5") (pinfunction "IN_5") (pintype "passive"))
      (node (ref "U6") (pin "3") (pinfunction "VIN_3") (pintype "passive"))
      (node (ref "U7") (pin "3") (pinfunction "Vcc_3") (pintype "passive"))
    )
    (net (code "42") (name "24V") (class "Default")
      (node (ref "C8") (pin "2") (pinfunction "2_2") (pintype "passive"))
      (node (ref "D1") (pin "2") (pinfunction "K_2") (pintype "passive"))
      (node (ref "J1") (pin "1") (pinfunction "1_1") (pintype "passive"))
      (node (ref "R16") (pin "1") (pinfunction "1_1") (pintype "passive"))
      (node (ref "R33") (pin "1") (pinfunction "1_1") (pintype "passive"))
      (node (ref "U2") (pin "3") (pinfunction "VIN_3") (pintype "passive"))
    )
    (net (code "43") (name "GND") (class "Default")
      (node (ref "C1") (pin "1") (pinfunction "1_1") (pintype "passive"))
      (node (ref "C12") (pin "1") (pinfunction "1_1") (pintype "passive"))
      (node (ref "C13") (pin "1") (pinfunction "1_1") (pintype "passive"))
      (node (ref "C14") (pin "1") (pinfunction "1_1") (pintype "passive"))
      (node (ref "C15") (pin "1") (pinfunction "1_1") (pintype "passive"))
      (node (ref "C16") (pin "1") (pinfunction "1_1") (pintype "passive"))
      (node (ref "C17") (pin "1") (pinfunction "1_1") (pintype "passive"))
      (node (ref "C18") (pin "1") (pinfunction "1_1") (pintype "passive"))
      (node (ref "C19") (pin "1") (pinfunction "1_1") (pintype "passive"))
      (node (ref "C2") (pin "1") (pinfunction "1_1") (pintype "passive"))
      (node (ref "C20") (pin "1") (pinfunction "1_1") (pintype "passive"))
      (node (ref "C21") (pin "1") (pinfunction "1_1") (pintype "passive"))
      (node (ref "C22") (pin "1") (pinfunction "1_1") (pintype "passive"))
      (node (ref "C23") (pin "1") (pinfunction "1_1") (pintype "passive"))
      (node (ref "C24") (pin "1") (pinfunction "1_1") (pintype "passive"))
      (node (ref "C25") (pin "1") (pinfunction "1_1") (pintype "passive"))
      (node (ref "C26") (pin "1") (pinfunction "1_1") (pintype "passive"))
      (node (ref "C27") (pin "1") (pinfunction "1_1") (pintype "passive"))
      (node (ref "C3") (pin "1") (pinfunction "1_1") (pintype "passive"))
      (node (ref "C4") (pin "1") (pinfunction "1_1") (pintype "passive"))
      (node (ref "C5") (pin "1") (pinfunction "1_1") (pintype "passive"))
      (node (ref "C6") (pin "1") (pinfunction "1_1") (pintype "passive"))
      (node (ref "C7") (pin "1") (pinfunction "1_1") (pintype "passive"))
      (node (ref "C8") (pin "1") (pinfunction "1_1") (pintype "passive"))
      (node (ref "C9") (pin "1") (pinfunction "1_1") (pintype "passive"))
      (node (ref "D1") (pin "1") (pinfunction "A_1") (pintype "passive"))
      (node (ref "D2") (pin "2") (pinfunction "K_2") (pintype "passive"))
      (node (ref "D3") (pin "3") (pinfunction "3_3") (pintype "passive"))
      (node (ref "J1") (pin "2") (pinfunction "2_2") (pintype "passive"))
      (node (ref "J3") (pin "3") (pinfunction "3_3") (pintype "passive"))
      (node (ref "J4") (pin "3") (pinfunction "3_3") (pintype "passive"))
      (node (ref "J5") (pin "4") (pinfunction "4_4") (pintype "passive"))
      (node (ref "J6") (pin "4") (pinfunction "4_4") (pintype "passive"))
      (node (ref "R11") (pin "2") (pinfunction "2_2") (pintype "passive"))
      (node (ref "R12") (pin "2") (pinfunction "2_2") (pintype "passive"))
      (node (ref "R13") (pin "2") (pinfunction "2_2") (pintype "passive"))
      (node (ref "R14") (pin "2") (pinfunction "2_2") (pintype "passive"))
      (node (ref "R15") (pin "2") (pinfunction "2_2") (pintype "passive"))
      (node (ref "R17") (pin "2") (pinfunction "2_2") (pintype "passive"))
      (node (ref "R22") (pin "2") (pinfunction "2_2") (pintype "passive"))
      (node (ref "R27") (pin "2") (pinfunction "2_2") (pintype "passive"))
      (node (ref "R28") (pin "2") (pinfunction "2_2") (pintype "passive"))
      (node (ref "R34") (pin "2") (pinfunction "2_2") (pintype "passive"))
      (node (ref "TP10") (pin "1") (pinfunction "1_1") (pintype "passive"))
      (node (ref "TP11") (pin "1") (pinfunction "1_1") (pintype "passive"))
      (node (ref "TP12") (pin "1") (pinfunction "1_1") (pintype "passive"))
      (node (ref "TP13") (pin "1") (pinfunction "1_1") (pintype "passive"))
      (node (ref "TP14") (pin "1") (pinfunction "1_1") (pintype "passive"))
      (node (ref "TP8") (pin "1") (pinfunction "1_1") (pintype "passive"))
      (node (ref "TP9") (pin "1") (pinfunction "1_1") (pintype "passive"))
      (node (ref "U1") (pin "23") (pinfunction "VSS_1_23") (pintype "passive"))
      (node (ref "U1") (pin "35") (pinfunction "VSS_2_35") (pintype "passive"))
      (node (ref "U1") (pin "44") (pinfunction "BOOT0_44") (pintype "passive"))
      (node (ref "U1") (pin "47") (pinfunction "VSS_3_47") (pintype "passive"))
      (node (ref "U1") (pin "8") (pinfunction "VSS_A_8") (pintype "passive"))
      (node (ref "U10") (pin "5") (pinfunction "GND_5") (pintype "passive"))
      (node (ref "U11") (pin "2") (pinfunction "GND_2") (pintype "passive"))
      (node (ref "U11") (pin "5") (pinfunction "WP_5") (pintype "passive"))
      (node (ref "U2") (pin "1") (pinfunction "GND_1") (pintype "passive"))
      (node (ref "U3") (pin "1") (pinfunction "GND_1") (pintype "passive"))
      (node (ref "U3") (pin "7") (pinfunction "GND_7") (pintype "passive"))
      (node (ref "U4") (pin "2") (pinfunction "GND_2") (pintype "passive"))
      (node (ref "U5") (pin "2") (pinfunction "GND_2") (pintype "passive"))
      (node (ref "U6") (pin "1") (pinfunction "VSS_1") (pintype "passive"))
      (node (ref "U7") (pin "2") (pinfunction "GND_2") (pintype "passive"))
      (node (ref "U7") (pin "8") (pinfunction "STB_8") (pintype "passive"))
      (node (ref "U7") (pin "9") (pinfunction "EP_9") (pintype "passive"))
      (node (ref "U8") (pin "1") (pinfunction "REF_1") (pintype "power_in"))
      (node (ref "U8") (pin "2") (pinfunction "GND_2") (pintype "power_in"))
      (node (ref "U9") (pin "1") (pinfunction "REF_1") (pintype "power_in"))
      (node (ref "U9") (pin "2") (pinfunction "GND_2") (pintype "power_in"))
    )
    (net (code "44") (name "Net-(C11-Pad2)") (class "Default")
      (node (ref "C11") (pin "2") (pinfunction "2_2") (pintype "passive"))
      (node (ref "R21") (pin "1") (pinfunction "1_1") (pintype "passive"))
      (node (ref "R23") (pin "2") (pinfunction "2_2") (pintype "passive"))
    )
    (net (code "45") (name "Net-(D2-A)") (class "Default")
      (node (ref "D2") (pin "1") (pinfunction "A_1") (pintype "passive"))
      (node (ref "R18") (pin "1") (pinfunction "1_1") (pintype "passive"))
    )
    (net (code "46") (name "Net-(J6-Pad1)") (class "Default")
      (node (ref "J6") (pin "1") (pinfunction "1_1") (pintype "passive"))
      (node (ref "R9") (pin "2") (pinfunction "2_2") (pintype "passive"))
    )
    (net (code "47") (name "Net-(J6-Pad2)") (class "Default")
      (node (ref "J6") (pin "2") (pinfunction "2_2") (pintype "passive"))
      (node (ref "R10") (pin "2") (pinfunction "2_2") (pintype "passive"))
    )
    (net (code "48") (name "Net-(R5-Pad1)") (class "Default")
      (node (ref "R5") (pin "1") (pinfunction "1_1") (pintype "passive"))
      (node (ref "TP1") (pin "1") (pinfunction "1_1") (pintype "passive"))
    )
    (net (code "49") (name "Net-(R6-Pad1)") (class "Default")
      (node (ref "R6") (pin "1") (pinfunction "1_1") (pintype "passive"))
      (node (ref "TP2") (pin "1") (pinfunction "1_1") (pintype "passive"))
    )
    (net (code "50") (name "Net-(R7-Pad1)") (class "Default")
      (node (ref "R7") (pin "1") (pinfunction "1_1") (pintype "passive"))
      (node (ref "TP3") (pin "1") (pinfunction "1_1") (pintype "passive"))
    )
    (net (code "51") (name "Net-(R8-Pad1)") (class "Default")
      (node (ref "R8") (pin "1") (pinfunction "1_1") (pintype "passive"))
      (node (ref "TP4") (pin "1") (pinfunction "1_1") (pintype "passive"))
    )
    (net (code "52") (name "Net-(U1-NRST)") (class "Default")
      (node (ref "C12") (pin "2") (pinfunction "2_2") (pintype "passive"))
      (node (ref "R26") (pin "2") (pinfunction "2_2") (pintype "passive"))
      (node (ref "U1") (pin "7") (pinfunction "NRST_7") (pintype "passive"))
    )
    (net (code "53") (name "Net-(U1-PB6)") (class "Default")
      (node (ref "R19") (pin "2") (pinfunction "2_2") (pintype "passive"))
      (node (ref "U1") (pin "42") (pinfunction "PB6_42") (pintype "passive"))
    )
    (net (code "54") (name "Net-(U1-PB7)") (class "Default")
      (node (ref "R20") (pin "2") (pinfunction "2_2") (pintype "passive"))
      (node (ref "U1") (pin "43") (pinfunction "PB7_43") (pintype "passive"))
    )
    (net (code "55") (name "Net-(U1-VDD_A)") (class "Default")
      (node (ref "C13") (pin "2") (pinfunction "2_2") (pintype "passive"))
      (node (ref "L2") (pin "2") (pinfunction "2_2") (pintype "passive"))
      (node (ref "U1") (pin "9") (pinfunction "VDD_A_9") (pintype "passive"))
    )
    (net (code "56") (name "Net-(U2-BOOT)") (class "Default")
      (node (ref "C10") (pin "1") (pinfunction "1_1") (pintype "passive"))
      (node (ref "U2") (pin "6") (pinfunction "BOOT_6") (pintype "passive"))
    )
    (net (code "57") (name "Net-(U2-EN)") (class "Default")
      (node (ref "R16") (pin "2") (pinfunction "2_2") (pintype "passive"))
      (node (ref "R17") (pin "1") (pinfunction "1_1") (pintype "passive"))
      (node (ref "U2") (pin "5") (pinfunction "EN_5") (pintype "passive"))
    )
    (net (code "58") (name "Net-(U2-FB)") (class "Default")
      (node (ref "C11") (pin "1") (pinfunction "1_1") (pintype "passive"))
      (node (ref "R21") (pin "2") (pinfunction "2_2") (pintype "passive"))
      (node (ref "R22") (pin "1") (pinfunction "1_1") (pintype "passive"))
      (node (ref "U2") (pin "4") (pinfunction "FB_4") (pintype "passive"))
    )
    (net (code "59") (name "Net-(U2-SW)") (class "Default")
      (node (ref "C10") (pin "2") (pinfunction "2_2") (pintype "passive"))
      (node (ref "L1") (pin "1") (pinfunction "1_1") (pintype "passive"))
      (node (ref "U2") (pin "2") (pinfunction "SW_2") (pintype "passive"))
    )
    (net (code "60") (name "Net-(U4-ISET)") (class "Default")
      (node (ref "R27") (pin "1") (pinfunction "1_1") (pintype "passive"))
      (node (ref "U4") (pin "3") (pinfunction "ISET_3") (pintype "passive"))
    )
    (net (code "61") (name "Net-(U4-OUT)") (class "Default")
      (node (ref "R29") (pin "2") (pinfunction "2_2") (pintype "passive"))
      (node (ref "U4") (pin "1") (pinfunction "OUT_1") (pintype "passive"))
      (node (ref "U8") (pin "4") (pinfunction "+_4") (pintype "passive"))
    )
    (net (code "62") (name "Net-(U5-ISET)") (class "Default")
      (node (ref "R28") (pin "1") (pinfunction "1_1") (pintype "passive"))
      (node (ref "U5") (pin "3") (pinfunction "ISET_3") (pintype "passive"))
    )
    (net (code "63") (name "Net-(U5-OUT)") (class "Default")
      (node (ref "R30") (pin "2") (pinfunction "2_2") (pintype "passive"))
      (node (ref "U5") (pin "1") (pinfunction "OUT_1") (pintype "passive"))
      (node (ref "U9") (pin "4") (pinfunction "+_4") (pintype "passive"))
    )
    (net (code "64") (name "Net-(U8-OUT)") (class "Default")
      (node (ref "R31") (pin "2") (pinfunction "2_2") (pintype "passive"))
      (node (ref "U8") (pin "6") (pinfunction "OUT_6") (pintype "passive"))
    )
    (net (code "65") (name "Net-(U9--)") (class "Default")
      (node (ref "R30") (pin "1") (pinfunction "1_1") (pintype "passive"))
      (node (ref "TP30") (pin "1") (pinfunction "1_1") (pintype "passive"))
      (node (ref "U9") (pin "5") (pinfunction "-_5") (pintype "passive"))
    )
    (net (code "66") (name "Net-(U9-OUT)") (class "Default")
      (node (ref "R32") (pin "2") (pinfunction "2_2") (pintype "passive"))
      (node (ref "U9") (pin "6") (pinfunction "OUT_6") (pintype "passive"))
    )
    (net (code "67") (name "SPWR") (class "Default")
      (node (ref "J6") (pin "3") (pinfunction "3_3") (pintype "passive"))
      (node (ref "R29") (pin "1") (pinfunction "1_1") (pintype "passive"))
      (node (ref "U8") (pin "5") (pinfunction "-_5") (pintype "passive"))
    )
  )
)
